# decade_resistance_box.net
KiCad netlist of a schematic drawn in EAGLE
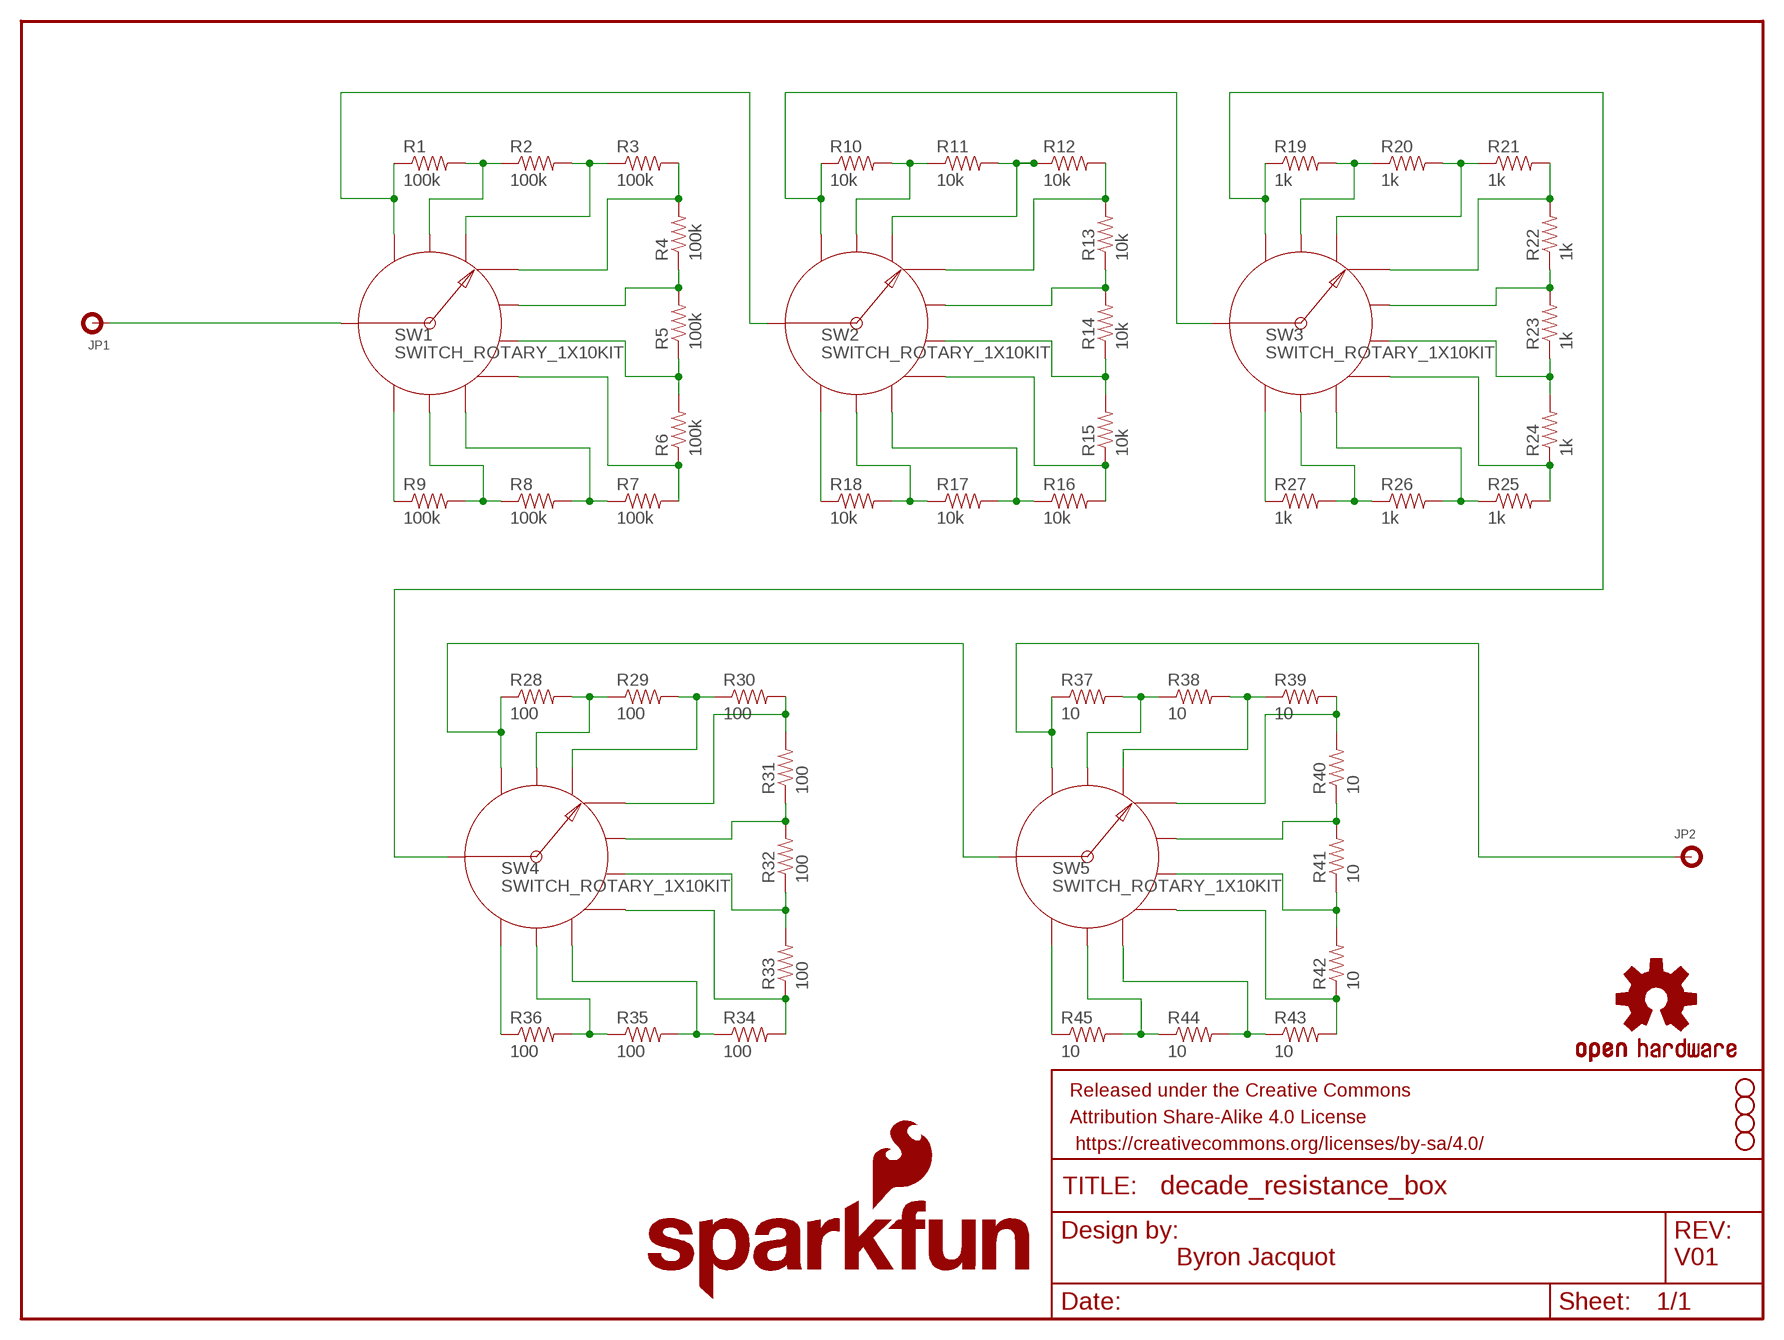
[diagram p0: schematic, sheet 1]

(export (version "E")
  (design (tool "Eeschema 10.0.6"))
  (components
    (comp (ref "FRAME1")
      (value "FRAME-LETTER")
      (footprint "eagle-import:CREATIVE_COMMONS")
      (libsource (lib "eagle-import") (part "FRAME-LETTER"))
    )
    (comp (ref "JP1")
      (value "BANANA-JACK")
      (footprint "eagle-import:BANANA-JACK")
      (libsource (lib "eagle-import") (part "BANANA-JACK"))
    )
    (comp (ref "JP2")
      (value "BANANA-JACK")
      (footprint "eagle-import:BANANA-JACK")
      (libsource (lib "eagle-import") (part "BANANA-JACK"))
    )
    (comp (ref "LOGO1")
      (value "OSHW-LOGOL")
      (footprint "eagle-import:OSHW-LOGO-L")
      (libsource (lib "eagle-import") (part "OSHW-LOGOL"))
    )
    (comp (ref "LOGO2")
      (value "SFE_LOGO_NAME_FLAME.2_INCH")
      (footprint "eagle-import:SFE_LOGO_NAME_FLAME_.2")
      (libsource (lib "eagle-import") (part "SFE_LOGO_NAME_FLAME.2_INCH"))
    )
    (comp (ref "LOGO3")
      (value "SFE_LOGO_NAME_FLAME.5_INCH")
      (footprint "eagle-import:SFE_LOGO_NAME_FLAME_.5")
      (libsource (lib "eagle-import") (part "SFE_LOGO_NAME_FLAME.5_INCH"))
    )
    (comp (ref "LOGO4")
      (value "OSHW-LOGOL")
      (footprint "eagle-import:OSHW-LOGO-L")
      (libsource (lib "eagle-import") (part "OSHW-LOGOL"))
    )
    (comp (ref "R1")
      (value "100k")
      (footprint "eagle-import:AXIAL-0.1EZ")
      (libsource (lib "eagle-import") (part "100KOHM-1/4W-1%(PTH)VERT-KIT"))
    )
    (comp (ref "R2")
      (value "100k")
      (footprint "eagle-import:AXIAL-0.1EZ")
      (libsource (lib "eagle-import") (part "100KOHM-1/4W-1%(PTH)VERT-KIT"))
    )
    (comp (ref "R3")
      (value "100k")
      (footprint "eagle-import:AXIAL-0.1EZ")
      (libsource (lib "eagle-import") (part "100KOHM-1/4W-1%(PTH)VERT-KIT"))
    )
    (comp (ref "R4")
      (value "100k")
      (footprint "eagle-import:AXIAL-0.1EZ")
      (libsource (lib "eagle-import") (part "100KOHM-1/4W-1%(PTH)VERT-KIT"))
    )
    (comp (ref "R5")
      (value "100k")
      (footprint "eagle-import:AXIAL-0.1EZ")
      (libsource (lib "eagle-import") (part "100KOHM-1/4W-1%(PTH)VERT-KIT"))
    )
    (comp (ref "R6")
      (value "100k")
      (footprint "eagle-import:AXIAL-0.1EZ")
      (libsource (lib "eagle-import") (part "100KOHM-1/4W-1%(PTH)VERT-KIT"))
    )
    (comp (ref "R7")
      (value "100k")
      (footprint "eagle-import:AXIAL-0.1EZ")
      (libsource (lib "eagle-import") (part "100KOHM-1/4W-1%(PTH)VERT-KIT"))
    )
    (comp (ref "R8")
      (value "100k")
      (footprint "eagle-import:AXIAL-0.1EZ")
      (libsource (lib "eagle-import") (part "100KOHM-1/4W-1%(PTH)VERT-KIT"))
    )
    (comp (ref "R9")
      (value "100k")
      (footprint "eagle-import:AXIAL-0.1EZ")
      (libsource (lib "eagle-import") (part "100KOHM-1/4W-1%(PTH)VERT-KIT"))
    )
    (comp (ref "R10")
      (value "10k")
      (footprint "eagle-import:AXIAL-0.1EZ")
      (libsource (lib "eagle-import") (part "10KOHM-1/4W-1%(PTH)VERT-KIT"))
    )
    (comp (ref "R11")
      (value "10k")
      (footprint "eagle-import:AXIAL-0.1EZ")
      (libsource (lib "eagle-import") (part "10KOHM-1/4W-1%(PTH)VERT-KIT"))
    )
    (comp (ref "R12")
      (value "10k")
      (footprint "eagle-import:AXIAL-0.1EZ")
      (libsource (lib "eagle-import") (part "10KOHM-1/4W-1%(PTH)VERT-KIT"))
    )
    (comp (ref "R13")
      (value "10k")
      (footprint "eagle-import:AXIAL-0.1EZ")
      (libsource (lib "eagle-import") (part "10KOHM-1/4W-1%(PTH)VERT-KIT"))
    )
    (comp (ref "R14")
      (value "10k")
      (footprint "eagle-import:AXIAL-0.1EZ")
      (libsource (lib "eagle-import") (part "10KOHM-1/4W-1%(PTH)VERT-KIT"))
    )
    (comp (ref "R15")
      (value "10k")
      (footprint "eagle-import:AXIAL-0.1EZ")
      (libsource (lib "eagle-import") (part "10KOHM-1/4W-1%(PTH)VERT-KIT"))
    )
    (comp (ref "R16")
      (value "10k")
      (footprint "eagle-import:AXIAL-0.1EZ")
      (libsource (lib "eagle-import") (part "10KOHM-1/4W-1%(PTH)VERT-KIT"))
    )
    (comp (ref "R17")
      (value "10k")
      (footprint "eagle-import:AXIAL-0.1EZ")
      (libsource (lib "eagle-import") (part "10KOHM-1/4W-1%(PTH)VERT-KIT"))
    )
    (comp (ref "R18")
      (value "10k")
      (footprint "eagle-import:AXIAL-0.1EZ")
      (libsource (lib "eagle-import") (part "10KOHM-1/4W-1%(PTH)VERT-KIT"))
    )
    (comp (ref "R19")
      (value "1k")
      (footprint "eagle-import:AXIAL-0.1EZ")
      (libsource (lib "eagle-import") (part "1KOHM-1/4W-1%(PTH)VERT-KIT"))
    )
    (comp (ref "R20")
      (value "1k")
      (footprint "eagle-import:AXIAL-0.1EZ")
      (libsource (lib "eagle-import") (part "1KOHM-1/4W-1%(PTH)VERT-KIT"))
    )
    (comp (ref "R21")
      (value "1k")
      (footprint "eagle-import:AXIAL-0.1EZ")
      (libsource (lib "eagle-import") (part "1KOHM-1/4W-1%(PTH)VERT-KIT"))
    )
    (comp (ref "R22")
      (value "1k")
      (footprint "eagle-import:AXIAL-0.1EZ")
      (libsource (lib "eagle-import") (part "1KOHM-1/4W-1%(PTH)VERT-KIT"))
    )
    (comp (ref "R23")
      (value "1k")
      (footprint "eagle-import:AXIAL-0.1EZ")
      (libsource (lib "eagle-import") (part "1KOHM-1/4W-1%(PTH)VERT-KIT"))
    )
    (comp (ref "R24")
      (value "1k")
      (footprint "eagle-import:AXIAL-0.1EZ")
      (libsource (lib "eagle-import") (part "1KOHM-1/4W-1%(PTH)VERT-KIT"))
    )
    (comp (ref "R25")
      (value "1k")
      (footprint "eagle-import:AXIAL-0.1EZ")
      (libsource (lib "eagle-import") (part "1KOHM-1/4W-1%(PTH)VERT-KIT"))
    )
    (comp (ref "R26")
      (value "1k")
      (footprint "eagle-import:AXIAL-0.1EZ")
      (libsource (lib "eagle-import") (part "1KOHM-1/4W-1%(PTH)VERT-KIT"))
    )
    (comp (ref "R27")
      (value "1k")
      (footprint "eagle-import:AXIAL-0.1EZ")
      (libsource (lib "eagle-import") (part "1KOHM-1/4W-1%(PTH)VERT-KIT"))
    )
    (comp (ref "R28")
      (value "100")
      (footprint "eagle-import:AXIAL-0.1EZ")
      (libsource (lib "eagle-import") (part "100OHM-1/4W-1%(PTH)VERT-KIT"))
    )
    (comp (ref "R29")
      (value "100")
      (footprint "eagle-import:AXIAL-0.1EZ")
      (libsource (lib "eagle-import") (part "100OHM-1/4W-1%(PTH)VERT-KIT"))
    )
    (comp (ref "R30")
      (value "100")
      (footprint "eagle-import:AXIAL-0.1EZ")
      (libsource (lib "eagle-import") (part "100OHM-1/4W-1%(PTH)VERT-KIT"))
    )
    (comp (ref "R31")
      (value "100")
      (footprint "eagle-import:AXIAL-0.1EZ")
      (libsource (lib "eagle-import") (part "100OHM-1/4W-1%(PTH)VERT-KIT"))
    )
    (comp (ref "R32")
      (value "100")
      (footprint "eagle-import:AXIAL-0.1EZ")
      (libsource (lib "eagle-import") (part "100OHM-1/4W-1%(PTH)VERT-KIT"))
    )
    (comp (ref "R33")
      (value "100")
      (footprint "eagle-import:AXIAL-0.1EZ")
      (libsource (lib "eagle-import") (part "100OHM-1/4W-1%(PTH)VERT-KIT"))
    )
    (comp (ref "R34")
      (value "100")
      (footprint "eagle-import:AXIAL-0.1EZ")
      (libsource (lib "eagle-import") (part "100OHM-1/4W-1%(PTH)VERT-KIT"))
    )
    (comp (ref "R35")
      (value "100")
      (footprint "eagle-import:AXIAL-0.1EZ")
      (libsource (lib "eagle-import") (part "100OHM-1/4W-1%(PTH)VERT-KIT"))
    )
    (comp (ref "R36")
      (value "100")
      (footprint "eagle-import:AXIAL-0.1EZ")
      (libsource (lib "eagle-import") (part "100OHM-1/4W-1%(PTH)VERT-KIT"))
    )
    (comp (ref "R37")
      (value "10")
      (footprint "eagle-import:AXIAL-0.1EZ")
      (libsource (lib "eagle-import") (part "10OHM-1/4W-1%(PTH)VERT-KIT"))
    )
    (comp (ref "R38")
      (value "10")
      (footprint "eagle-import:AXIAL-0.1EZ")
      (libsource (lib "eagle-import") (part "10OHM-1/4W-1%(PTH)VERT-KIT"))
    )
    (comp (ref "R39")
      (value "10")
      (footprint "eagle-import:AXIAL-0.1EZ")
      (libsource (lib "eagle-import") (part "10OHM-1/4W-1%(PTH)VERT-KIT"))
    )
    (comp (ref "R40")
      (value "10")
      (footprint "eagle-import:AXIAL-0.1EZ")
      (libsource (lib "eagle-import") (part "10OHM-1/4W-1%(PTH)VERT-KIT"))
    )
    (comp (ref "R41")
      (value "10")
      (footprint "eagle-import:AXIAL-0.1EZ")
      (libsource (lib "eagle-import") (part "10OHM-1/4W-1%(PTH)VERT-KIT"))
    )
    (comp (ref "R42")
      (value "10")
      (footprint "eagle-import:AXIAL-0.1EZ")
      (libsource (lib "eagle-import") (part "10OHM-1/4W-1%(PTH)VERT-KIT"))
    )
    (comp (ref "R43")
      (value "10")
      (footprint "eagle-import:AXIAL-0.1EZ")
      (libsource (lib "eagle-import") (part "10OHM-1/4W-1%(PTH)VERT-KIT"))
    )
    (comp (ref "R44")
      (value "10")
      (footprint "eagle-import:AXIAL-0.1EZ")
      (libsource (lib "eagle-import") (part "10OHM-1/4W-1%(PTH)VERT-KIT"))
    )
    (comp (ref "R45")
      (value "10")
      (footprint "eagle-import:AXIAL-0.1EZ")
      (libsource (lib "eagle-import") (part "10OHM-1/4W-1%(PTH)VERT-KIT"))
    )
    (comp (ref "STANDOFF1")
      (value "STAND-OFF")
      (footprint "eagle-import:STAND-OFF")
      (libsource (lib "eagle-import") (part "STAND-OFF"))
    )
    (comp (ref "STANDOFF2")
      (value "STAND-OFF")
      (footprint "eagle-import:STAND-OFF")
      (libsource (lib "eagle-import") (part "STAND-OFF"))
    )
    (comp (ref "STANDOFF3")
      (value "STAND-OFF")
      (footprint "eagle-import:STAND-OFF")
      (libsource (lib "eagle-import") (part "STAND-OFF"))
    )
    (comp (ref "STANDOFF4")
      (value "STAND-OFF")
      (footprint "eagle-import:STAND-OFF")
      (libsource (lib "eagle-import") (part "STAND-OFF"))
    )
    (comp (ref "SW1")
      (value "SWITCH_ROTARY_1X10KIT")
      (footprint "eagle-import:ROTARY_SWITCH_1X10_KIT")
      (libsource (lib "eagle-import") (part "SWITCH_ROTARY_1X10KIT"))
    )
    (comp (ref "SW2")
      (value "SWITCH_ROTARY_1X10KIT")
      (footprint "eagle-import:ROTARY_SWITCH_1X10_KIT")
      (libsource (lib "eagle-import") (part "SWITCH_ROTARY_1X10KIT"))
    )
    (comp (ref "SW3")
      (value "SWITCH_ROTARY_1X10KIT")
      (footprint "eagle-import:ROTARY_SWITCH_1X10_KIT")
      (libsource (lib "eagle-import") (part "SWITCH_ROTARY_1X10KIT"))
    )
    (comp (ref "SW4")
      (value "SWITCH_ROTARY_1X10KIT")
      (footprint "eagle-import:ROTARY_SWITCH_1X10_KIT")
      (libsource (lib "eagle-import") (part "SWITCH_ROTARY_1X10KIT"))
    )
    (comp (ref "SW5")
      (value "SWITCH_ROTARY_1X10KIT")
      (footprint "eagle-import:ROTARY_SWITCH_1X10_KIT")
      (libsource (lib "eagle-import") (part "SWITCH_ROTARY_1X10KIT"))
    )
  )
  (nets
    (net (code "1") (name "Net-(JP1-PadP$1)") (class "Default")
      (node (ref "JP1") (pin "P$1") (pinfunction "P$1_P$1") (pintype "bidirectional"))
      (node (ref "SW1") (pin "COMMON") (pinfunction "COMMON_COMMON") (pintype "bidirectional"))
    )
    (net (code "2") (name "Net-(R1-1)") (class "Default")
      (node (ref "R1") (pin "P$1") (pinfunction "1_P$1") (pintype "passive"))
      (node (ref "SW1") (pin "1") (pinfunction "1_1") (pintype "bidirectional"))
      (node (ref "SW2") (pin "COMMON") (pinfunction "COMMON_COMMON") (pintype "bidirectional"))
    )
    (net (code "3") (name "Net-(R1-2)") (class "Default")
      (node (ref "R1") (pin "P$2") (pinfunction "2_P$2") (pintype "passive"))
      (node (ref "R2") (pin "P$1") (pinfunction "1_P$1") (pintype "passive"))
      (node (ref "SW1") (pin "2") (pinfunction "2_2") (pintype "bidirectional"))
    )
    (net (code "4") (name "Net-(R2-2)") (class "Default")
      (node (ref "R2") (pin "P$2") (pinfunction "2_P$2") (pintype "passive"))
      (node (ref "R3") (pin "P$1") (pinfunction "1_P$1") (pintype "passive"))
      (node (ref "SW1") (pin "3") (pinfunction "3_3") (pintype "bidirectional"))
    )
    (net (code "5") (name "Net-(R3-2)") (class "Default")
      (node (ref "R3") (pin "P$2") (pinfunction "2_P$2") (pintype "passive"))
      (node (ref "R4") (pin "P$2") (pinfunction "2_P$2") (pintype "passive"))
      (node (ref "SW1") (pin "4") (pinfunction "4_4") (pintype "bidirectional"))
    )
    (net (code "6") (name "Net-(R4-1)") (class "Default")
      (node (ref "R4") (pin "P$1") (pinfunction "1_P$1") (pintype "passive"))
      (node (ref "R5") (pin "P$2") (pinfunction "2_P$2") (pintype "passive"))
      (node (ref "SW1") (pin "5") (pinfunction "5_5") (pintype "bidirectional"))
    )
    (net (code "7") (name "Net-(R5-1)") (class "Default")
      (node (ref "R5") (pin "P$1") (pinfunction "1_P$1") (pintype "passive"))
      (node (ref "R6") (pin "P$2") (pinfunction "2_P$2") (pintype "passive"))
      (node (ref "SW1") (pin "6") (pinfunction "6_6") (pintype "bidirectional"))
    )
    (net (code "8") (name "Net-(R6-1)") (class "Default")
      (node (ref "R6") (pin "P$1") (pinfunction "1_P$1") (pintype "passive"))
      (node (ref "R7") (pin "P$2") (pinfunction "2_P$2") (pintype "passive"))
      (node (ref "SW1") (pin "7") (pinfunction "7_7") (pintype "bidirectional"))
    )
    (net (code "9") (name "Net-(R7-1)") (class "Default")
      (node (ref "R7") (pin "P$1") (pinfunction "1_P$1") (pintype "passive"))
      (node (ref "R8") (pin "P$2") (pinfunction "2_P$2") (pintype "passive"))
      (node (ref "SW1") (pin "8") (pinfunction "8_8") (pintype "bidirectional"))
    )
    (net (code "10") (name "Net-(R8-1)") (class "Default")
      (node (ref "R8") (pin "P$1") (pinfunction "1_P$1") (pintype "passive"))
      (node (ref "R9") (pin "P$2") (pinfunction "2_P$2") (pintype "passive"))
      (node (ref "SW1") (pin "9") (pinfunction "9_9") (pintype "bidirectional"))
    )
    (net (code "11") (name "Net-(R9-1)") (class "Default")
      (node (ref "R9") (pin "P$1") (pinfunction "1_P$1") (pintype "passive"))
      (node (ref "SW1") (pin "10") (pinfunction "10_10") (pintype "bidirectional"))
    )
    (net (code "12") (name "Net-(R10-1)") (class "Default")
      (node (ref "R10") (pin "P$1") (pinfunction "1_P$1") (pintype "passive"))
      (node (ref "SW2") (pin "1") (pinfunction "1_1") (pintype "bidirectional"))
      (node (ref "SW3") (pin "COMMON") (pinfunction "COMMON_COMMON") (pintype "bidirectional"))
    )
    (net (code "13") (name "Net-(R10-2)") (class "Default")
      (node (ref "R10") (pin "P$2") (pinfunction "2_P$2") (pintype "passive"))
      (node (ref "R11") (pin "P$1") (pinfunction "1_P$1") (pintype "passive"))
      (node (ref "SW2") (pin "2") (pinfunction "2_2") (pintype "bidirectional"))
    )
    (net (code "14") (name "Net-(R11-2)") (class "Default")
      (node (ref "R11") (pin "P$2") (pinfunction "2_P$2") (pintype "passive"))
      (node (ref "R12") (pin "P$1") (pinfunction "1_P$1") (pintype "passive"))
      (node (ref "SW2") (pin "3") (pinfunction "3_3") (pintype "bidirectional"))
    )
    (net (code "15") (name "Net-(R12-2)") (class "Default")
      (node (ref "R12") (pin "P$2") (pinfunction "2_P$2") (pintype "passive"))
      (node (ref "R13") (pin "P$2") (pinfunction "2_P$2") (pintype "passive"))
      (node (ref "SW2") (pin "4") (pinfunction "4_4") (pintype "bidirectional"))
    )
    (net (code "16") (name "Net-(R13-1)") (class "Default")
      (node (ref "R13") (pin "P$1") (pinfunction "1_P$1") (pintype "passive"))
      (node (ref "R14") (pin "P$2") (pinfunction "2_P$2") (pintype "passive"))
      (node (ref "SW2") (pin "5") (pinfunction "5_5") (pintype "bidirectional"))
    )
    (net (code "17") (name "Net-(R14-1)") (class "Default")
      (node (ref "R14") (pin "P$1") (pinfunction "1_P$1") (pintype "passive"))
      (node (ref "R15") (pin "P$2") (pinfunction "2_P$2") (pintype "passive"))
      (node (ref "SW2") (pin "6") (pinfunction "6_6") (pintype "bidirectional"))
    )
    (net (code "18") (name "Net-(R15-1)") (class "Default")
      (node (ref "R15") (pin "P$1") (pinfunction "1_P$1") (pintype "passive"))
      (node (ref "R16") (pin "P$2") (pinfunction "2_P$2") (pintype "passive"))
      (node (ref "SW2") (pin "7") (pinfunction "7_7") (pintype "bidirectional"))
    )
    (net (code "19") (name "Net-(R16-1)") (class "Default")
      (node (ref "R16") (pin "P$1") (pinfunction "1_P$1") (pintype "passive"))
      (node (ref "R17") (pin "P$2") (pinfunction "2_P$2") (pintype "passive"))
      (node (ref "SW2") (pin "8") (pinfunction "8_8") (pintype "bidirectional"))
    )
    (net (code "20") (name "Net-(R17-1)") (class "Default")
      (node (ref "R17") (pin "P$1") (pinfunction "1_P$1") (pintype "passive"))
      (node (ref "R18") (pin "P$2") (pinfunction "2_P$2") (pintype "passive"))
      (node (ref "SW2") (pin "9") (pinfunction "9_9") (pintype "bidirectional"))
    )
    (net (code "21") (name "Net-(R18-1)") (class "Default")
      (node (ref "R18") (pin "P$1") (pinfunction "1_P$1") (pintype "passive"))
      (node (ref "SW2") (pin "10") (pinfunction "10_10") (pintype "bidirectional"))
    )
    (net (code "22") (name "Net-(R19-1)") (class "Default")
      (node (ref "R19") (pin "P$1") (pinfunction "1_P$1") (pintype "passive"))
      (node (ref "SW3") (pin "1") (pinfunction "1_1") (pintype "bidirectional"))
      (node (ref "SW4") (pin "COMMON") (pinfunction "COMMON_COMMON") (pintype "bidirectional"))
    )
    (net (code "23") (name "Net-(R19-2)") (class "Default")
      (node (ref "R19") (pin "P$2") (pinfunction "2_P$2") (pintype "passive"))
      (node (ref "R20") (pin "P$1") (pinfunction "1_P$1") (pintype "passive"))
      (node (ref "SW3") (pin "2") (pinfunction "2_2") (pintype "bidirectional"))
    )
    (net (code "24") (name "Net-(R20-2)") (class "Default")
      (node (ref "R20") (pin "P$2") (pinfunction "2_P$2") (pintype "passive"))
      (node (ref "R21") (pin "P$1") (pinfunction "1_P$1") (pintype "passive"))
      (node (ref "SW3") (pin "3") (pinfunction "3_3") (pintype "bidirectional"))
    )
    (net (code "25") (name "Net-(R21-2)") (class "Default")
      (node (ref "R21") (pin "P$2") (pinfunction "2_P$2") (pintype "passive"))
      (node (ref "R22") (pin "P$2") (pinfunction "2_P$2") (pintype "passive"))
      (node (ref "SW3") (pin "4") (pinfunction "4_4") (pintype "bidirectional"))
    )
    (net (code "26") (name "Net-(R22-1)") (class "Default")
      (node (ref "R22") (pin "P$1") (pinfunction "1_P$1") (pintype "passive"))
      (node (ref "R23") (pin "P$2") (pinfunction "2_P$2") (pintype "passive"))
      (node (ref "SW3") (pin "5") (pinfunction "5_5") (pintype "bidirectional"))
    )
    (net (code "27") (name "Net-(R23-1)") (class "Default")
      (node (ref "R23") (pin "P$1") (pinfunction "1_P$1") (pintype "passive"))
      (node (ref "R24") (pin "P$2") (pinfunction "2_P$2") (pintype "passive"))
      (node (ref "SW3") (pin "6") (pinfunction "6_6") (pintype "bidirectional"))
    )
    (net (code "28") (name "Net-(R24-1)") (class "Default")
      (node (ref "R24") (pin "P$1") (pinfunction "1_P$1") (pintype "passive"))
      (node (ref "R25") (pin "P$2") (pinfunction "2_P$2") (pintype "passive"))
      (node (ref "SW3") (pin "7") (pinfunction "7_7") (pintype "bidirectional"))
    )
    (net (code "29") (name "Net-(R25-1)") (class "Default")
      (node (ref "R25") (pin "P$1") (pinfunction "1_P$1") (pintype "passive"))
      (node (ref "R26") (pin "P$2") (pinfunction "2_P$2") (pintype "passive"))
      (node (ref "SW3") (pin "8") (pinfunction "8_8") (pintype "bidirectional"))
    )
    (net (code "30") (name "Net-(R26-1)") (class "Default")
      (node (ref "R26") (pin "P$1") (pinfunction "1_P$1") (pintype "passive"))
      (node (ref "R27") (pin "P$2") (pinfunction "2_P$2") (pintype "passive"))
      (node (ref "SW3") (pin "9") (pinfunction "9_9") (pintype "bidirectional"))
    )
    (net (code "31") (name "Net-(R27-1)") (class "Default")
      (node (ref "R27") (pin "P$1") (pinfunction "1_P$1") (pintype "passive"))
      (node (ref "SW3") (pin "10") (pinfunction "10_10") (pintype "bidirectional"))
    )
    (net (code "32") (name "Net-(R28-1)") (class "Default")
      (node (ref "R28") (pin "P$1") (pinfunction "1_P$1") (pintype "passive"))
      (node (ref "SW4") (pin "1") (pinfunction "1_1") (pintype "bidirectional"))
      (node (ref "SW5") (pin "COMMON") (pinfunction "COMMON_COMMON") (pintype "bidirectional"))
    )
    (net (code "33") (name "Net-(R28-2)") (class "Default")
      (node (ref "R28") (pin "P$2") (pinfunction "2_P$2") (pintype "passive"))
      (node (ref "R29") (pin "P$1") (pinfunction "1_P$1") (pintype "passive"))
      (node (ref "SW4") (pin "2") (pinfunction "2_2") (pintype "bidirectional"))
    )
    (net (code "34") (name "Net-(R29-2)") (class "Default")
      (node (ref "R29") (pin "P$2") (pinfunction "2_P$2") (pintype "passive"))
      (node (ref "R30") (pin "P$1") (pinfunction "1_P$1") (pintype "passive"))
      (node (ref "SW4") (pin "3") (pinfunction "3_3") (pintype "bidirectional"))
    )
    (net (code "35") (name "Net-(R30-2)") (class "Default")
      (node (ref "R30") (pin "P$2") (pinfunction "2_P$2") (pintype "passive"))
      (node (ref "R31") (pin "P$2") (pinfunction "2_P$2") (pintype "passive"))
      (node (ref "SW4") (pin "4") (pinfunction "4_4") (pintype "bidirectional"))
    )
    (net (code "36") (name "Net-(R31-1)") (class "Default")
      (node (ref "R31") (pin "P$1") (pinfunction "1_P$1") (pintype "passive"))
      (node (ref "R32") (pin "P$2") (pinfunction "2_P$2") (pintype "passive"))
      (node (ref "SW4") (pin "5") (pinfunction "5_5") (pintype "bidirectional"))
    )
    (net (code "37") (name "Net-(R32-1)") (class "Default")
      (node (ref "R32") (pin "P$1") (pinfunction "1_P$1") (pintype "passive"))
      (node (ref "R33") (pin "P$2") (pinfunction "2_P$2") (pintype "passive"))
      (node (ref "SW4") (pin "6") (pinfunction "6_6") (pintype "bidirectional"))
    )
    (net (code "38") (name "Net-(R33-1)") (class "Default")
      (node (ref "R33") (pin "P$1") (pinfunction "1_P$1") (pintype "passive"))
      (node (ref "R34") (pin "P$2") (pinfunction "2_P$2") (pintype "passive"))
      (node (ref "SW4") (pin "7") (pinfunction "7_7") (pintype "bidirectional"))
    )
    (net (code "39") (name "Net-(R34-1)") (class "Default")
      (node (ref "R34") (pin "P$1") (pinfunction "1_P$1") (pintype "passive"))
      (node (ref "R35") (pin "P$2") (pinfunction "2_P$2") (pintype "passive"))
      (node (ref "SW4") (pin "8") (pinfunction "8_8") (pintype "bidirectional"))
    )
    (net (code "40") (name "Net-(R35-1)") (class "Default")
      (node (ref "R35") (pin "P$1") (pinfunction "1_P$1") (pintype "passive"))
      (node (ref "R36") (pin "P$2") (pinfunction "2_P$2") (pintype "passive"))
      (node (ref "SW4") (pin "9") (pinfunction "9_9") (pintype "bidirectional"))
    )
    (net (code "41") (name "Net-(R36-1)") (class "Default")
      (node (ref "R36") (pin "P$1") (pinfunction "1_P$1") (pintype "passive"))
      (node (ref "SW4") (pin "10") (pinfunction "10_10") (pintype "bidirectional"))
    )
    (net (code "42") (name "Net-(R37-1)") (class "Default")
      (node (ref "JP2") (pin "P$1") (pinfunction "P$1_P$1") (pintype "bidirectional"))
      (node (ref "R37") (pin "P$1") (pinfunction "1_P$1") (pintype "passive"))
      (node (ref "SW5") (pin "1") (pinfunction "1_1") (pintype "bidirectional"))
    )
    (net (code "43") (name "Net-(R37-2)") (class "Default")
      (node (ref "R37") (pin "P$2") (pinfunction "2_P$2") (pintype "passive"))
      (node (ref "R38") (pin "P$1") (pinfunction "1_P$1") (pintype "passive"))
      (node (ref "SW5") (pin "2") (pinfunction "2_2") (pintype "bidirectional"))
    )
    (net (code "44") (name "Net-(R38-2)") (class "Default")
      (node (ref "R38") (pin "P$2") (pinfunction "2_P$2") (pintype "passive"))
      (node (ref "R39") (pin "P$1") (pinfunction "1_P$1") (pintype "passive"))
      (node (ref "SW5") (pin "3") (pinfunction "3_3") (pintype "bidirectional"))
    )
    (net (code "45") (name "Net-(R39-2)") (class "Default")
      (node (ref "R39") (pin "P$2") (pinfunction "2_P$2") (pintype "passive"))
      (node (ref "R40") (pin "P$2") (pinfunction "2_P$2") (pintype "passive"))
      (node (ref "SW5") (pin "4") (pinfunction "4_4") (pintype "bidirectional"))
    )
    (net (code "46") (name "Net-(R40-1)") (class "Default")
      (node (ref "R40") (pin "P$1") (pinfunction "1_P$1") (pintype "passive"))
      (node (ref "R41") (pin "P$2") (pinfunction "2_P$2") (pintype "passive"))
      (node (ref "SW5") (pin "5") (pinfunction "5_5") (pintype "bidirectional"))
    )
    (net (code "47") (name "Net-(R41-1)") (class "Default")
      (node (ref "R41") (pin "P$1") (pinfunction "1_P$1") (pintype "passive"))
      (node (ref "R42") (pin "P$2") (pinfunction "2_P$2") (pintype "passive"))
      (node (ref "SW5") (pin "6") (pinfunction "6_6") (pintype "bidirectional"))
    )
    (net (code "48") (name "Net-(R42-1)") (class "Default")
      (node (ref "R42") (pin "P$1") (pinfunction "1_P$1") (pintype "passive"))
      (node (ref "R43") (pin "P$2") (pinfunction "2_P$2") (pintype "passive"))
      (node (ref "SW5") (pin "7") (pinfunction "7_7") (pintype "bidirectional"))
    )
    (net (code "49") (name "Net-(R43-1)") (class "Default")
      (node (ref "R43") (pin "P$1") (pinfunction "1_P$1") (pintype "passive"))
      (node (ref "R44") (pin "P$2") (pinfunction "2_P$2") (pintype "passive"))
      (node (ref "SW5") (pin "8") (pinfunction "8_8") (pintype "bidirectional"))
    )
    (net (code "50") (name "Net-(R44-1)") (class "Default")
      (node (ref "R44") (pin "P$1") (pinfunction "1_P$1") (pintype "passive"))
      (node (ref "R45") (pin "P$2") (pinfunction "2_P$2") (pintype "passive"))
      (node (ref "SW5") (pin "9") (pinfunction "9_9") (pintype "bidirectional"))
    )
    (net (code "51") (name "Net-(R45-1)") (class "Default")
      (node (ref "R45") (pin "P$1") (pinfunction "1_P$1") (pintype "passive"))
      (node (ref "SW5") (pin "10") (pinfunction "10_10") (pintype "bidirectional"))
    )
  )
)
